# buffer.net
KiCad netlist of a schematic drawn in Altium Designer
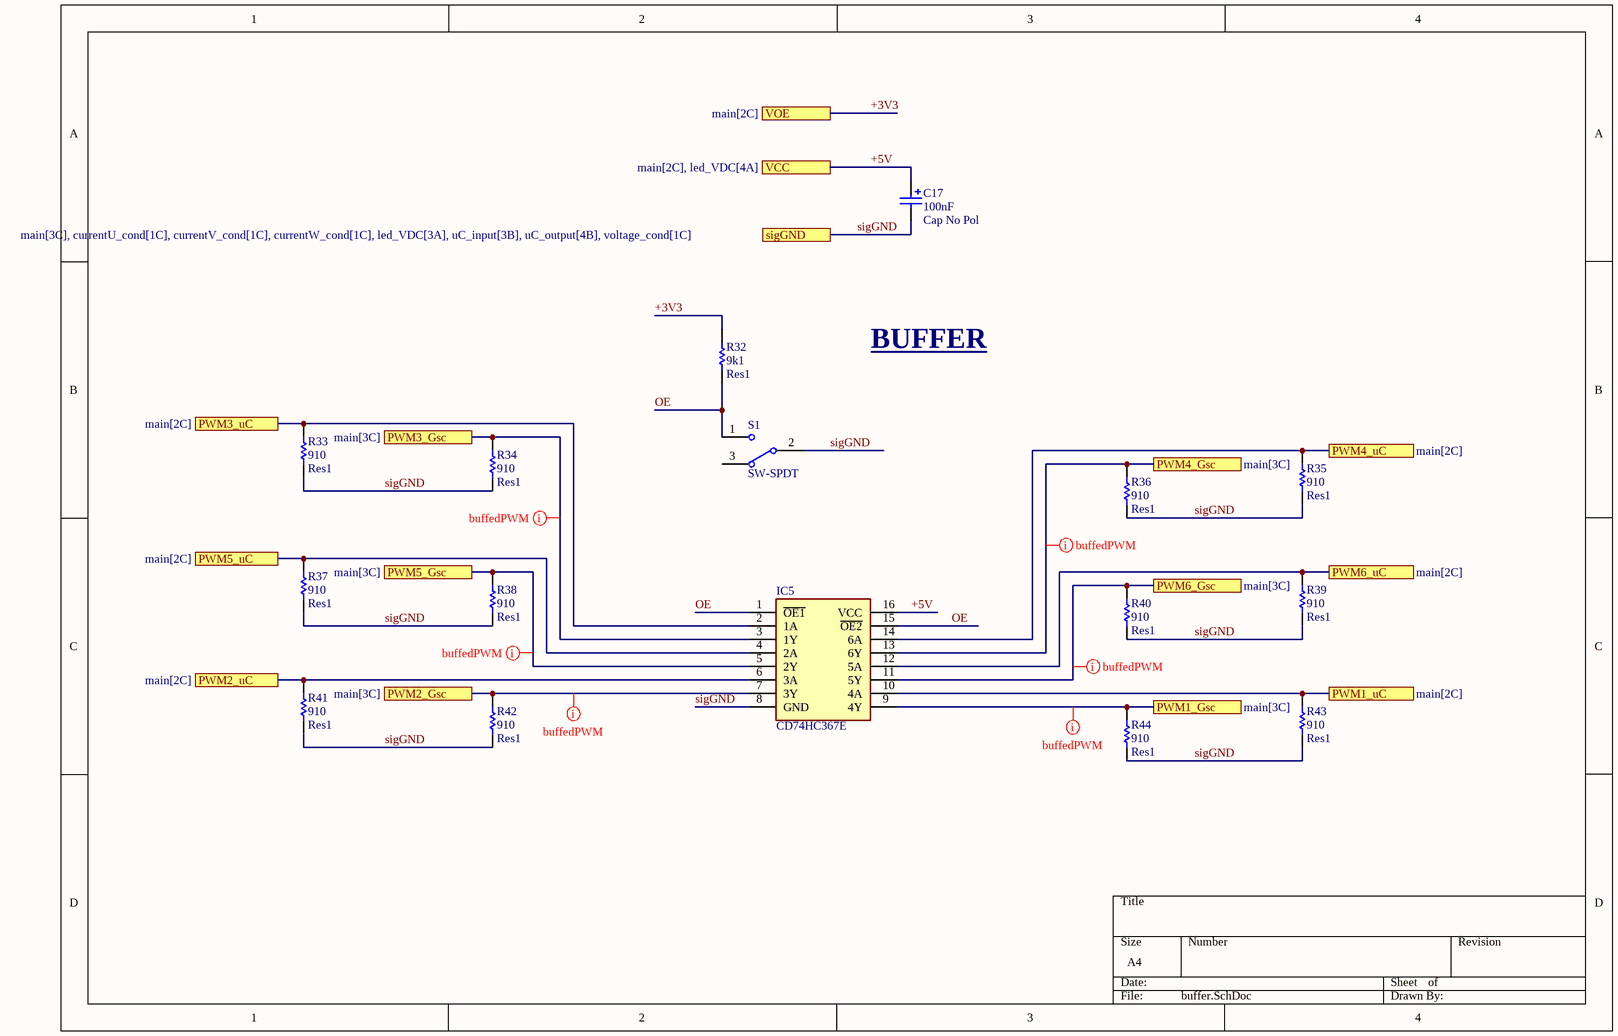
[diagram p0: buffer.SchDoc]

(export (version "E")
  (design (tool "Eeschema 10.0.6"))
  (components
    (comp (ref "C17")
      (value "Cap No Pol")
      (footprint "RAD-0.1_mod")
      (description "Polarized Capacitor (Radial)")
      (fields (field (name "ALTIUM_VALUE") "100nF") (field (name "PUBLISHER") "Altium Limited"))
      (libsource (lib "LABSTEPS_Project") (part "Cap No Pol"))
    )
    (comp (ref "IC5")
      (value "CD74HC367E")
      (footprint "DIP-16_mod")
      (description "Integrated Circuit")
      (fields (field (name "MOUSER PART NUMBER") "595-CD74HC367E"))
      (libsource (lib "SamacSys") (part "CD74HC367E"))
    )
    (comp (ref "R32")
      (value "Res1")
      (footprint "AXIAL-0.3_mod")
      (description "Resistor")
      (fields (field (name "ALTIUM_VALUE") "9k1") (field (name "PUBLISHER") "Altium Limited"))
      (libsource (lib "LABSTEPS_Project") (part "Res1"))
    )
    (comp (ref "R33")
      (value "Res1")
      (footprint "AXIAL-0.3_mod")
      (description "Resistor")
      (fields (field (name "ALTIUM_VALUE") "910") (field (name "PUBLISHER") "Altium Limited"))
      (libsource (lib "LABSTEPS_Project") (part "Res1"))
    )
    (comp (ref "R34")
      (value "Res1")
      (footprint "AXIAL-0.3_mod")
      (description "Resistor")
      (fields (field (name "ALTIUM_VALUE") "910") (field (name "PUBLISHER") "Altium Limited"))
      (libsource (lib "LABSTEPS_Project") (part "Res1"))
    )
    (comp (ref "R35")
      (value "Res1")
      (footprint "AXIAL-0.3_mod")
      (description "Resistor")
      (fields (field (name "ALTIUM_VALUE") "910") (field (name "PUBLISHER") "Altium Limited"))
      (libsource (lib "LABSTEPS_Project") (part "Res1"))
    )
    (comp (ref "R36")
      (value "Res1")
      (footprint "AXIAL-0.3_mod")
      (description "Resistor")
      (fields (field (name "ALTIUM_VALUE") "910") (field (name "PUBLISHER") "Altium Limited"))
      (libsource (lib "LABSTEPS_Project") (part "Res1"))
    )
    (comp (ref "R37")
      (value "Res1")
      (footprint "AXIAL-0.3_mod")
      (description "Resistor")
      (fields (field (name "ALTIUM_VALUE") "910") (field (name "PUBLISHER") "Altium Limited"))
      (libsource (lib "LABSTEPS_Project") (part "Res1"))
    )
    (comp (ref "R38")
      (value "Res1")
      (footprint "AXIAL-0.3_mod")
      (description "Resistor")
      (fields (field (name "ALTIUM_VALUE") "910") (field (name "PUBLISHER") "Altium Limited"))
      (libsource (lib "LABSTEPS_Project") (part "Res1"))
    )
    (comp (ref "R39")
      (value "Res1")
      (footprint "AXIAL-0.3_mod")
      (description "Resistor")
      (fields (field (name "ALTIUM_VALUE") "910") (field (name "PUBLISHER") "Altium Limited"))
      (libsource (lib "LABSTEPS_Project") (part "Res1"))
    )
    (comp (ref "R40")
      (value "Res1")
      (footprint "AXIAL-0.3_mod")
      (description "Resistor")
      (fields (field (name "ALTIUM_VALUE") "910") (field (name "PUBLISHER") "Altium Limited"))
      (libsource (lib "LABSTEPS_Project") (part "Res1"))
    )
    (comp (ref "R41")
      (value "Res1")
      (footprint "AXIAL-0.3_mod")
      (description "Resistor")
      (fields (field (name "ALTIUM_VALUE") "910") (field (name "PUBLISHER") "Altium Limited"))
      (libsource (lib "LABSTEPS_Project") (part "Res1"))
    )
    (comp (ref "R42")
      (value "Res1")
      (footprint "AXIAL-0.3_mod")
      (description "Resistor")
      (fields (field (name "ALTIUM_VALUE") "910") (field (name "PUBLISHER") "Altium Limited"))
      (libsource (lib "LABSTEPS_Project") (part "Res1"))
    )
    (comp (ref "R43")
      (value "Res1")
      (footprint "AXIAL-0.3_mod")
      (description "Resistor")
      (fields (field (name "ALTIUM_VALUE") "910") (field (name "PUBLISHER") "Altium Limited"))
      (libsource (lib "LABSTEPS_Project") (part "Res1"))
    )
    (comp (ref "R44")
      (value "Res1")
      (footprint "AXIAL-0.3_mod")
      (description "Resistor")
      (fields (field (name "ALTIUM_VALUE") "910") (field (name "PUBLISHER") "Altium Limited"))
      (libsource (lib "LABSTEPS_Project") (part "Res1"))
    )
    (comp (ref "S1")
      (value "SW-SPDT")
      (footprint "MHDR1X3_mod")
      (description "SPDT Subminiature Toggle Switch, Right Angle Mounting, Vertical Actuation")
      (fields (field (name "PUBLISHER") "Altium Limited"))
      (libsource (lib "LABSTEPS_Project") (part "SW-SPDT"))
    )
  )
  (nets
    (net (code "1") (name "/+3V3") (class "Default")
      (node (ref "R32") (pin "2") (pinfunction "2_2") (pintype "passive"))
    )
    (net (code "2") (name "/+5V") (class "Default")
      (node (ref "C17") (pin "1") (pinfunction "1_1") (pintype "passive"))
      (node (ref "IC5") (pin "16") (pinfunction "VCC_16") (pintype "passive"))
    )
    (net (code "3") (name "/OE") (class "Default")
      (node (ref "IC5") (pin "1") (pinfunction "~{OE1}_1") (pintype "passive"))
      (node (ref "IC5") (pin "15") (pinfunction "~{OE2}_15") (pintype "passive"))
      (node (ref "R32") (pin "1") (pinfunction "1_1") (pintype "passive"))
      (node (ref "S1") (pin "1") (pinfunction "1_1") (pintype "passive"))
    )
    (net (code "4") (name "/PWM1_Gsc") (class "Default")
      (node (ref "IC5") (pin "9") (pinfunction "4Y_9") (pintype "passive"))
      (node (ref "R44") (pin "2") (pinfunction "2_2") (pintype "passive"))
    )
    (net (code "5") (name "/PWM1_uC") (class "Default")
      (node (ref "IC5") (pin "10") (pinfunction "4A_10") (pintype "passive"))
      (node (ref "R43") (pin "2") (pinfunction "2_2") (pintype "passive"))
    )
    (net (code "6") (name "/PWM2_Gsc") (class "Default")
      (node (ref "IC5") (pin "7") (pinfunction "3Y_7") (pintype "passive"))
      (node (ref "R42") (pin "2") (pinfunction "2_2") (pintype "passive"))
    )
    (net (code "7") (name "/PWM2_uC") (class "Default")
      (node (ref "IC5") (pin "6") (pinfunction "3A_6") (pintype "passive"))
      (node (ref "R41") (pin "2") (pinfunction "2_2") (pintype "passive"))
    )
    (net (code "8") (name "/PWM3_Gsc") (class "Default")
      (node (ref "IC5") (pin "3") (pinfunction "1Y_3") (pintype "passive"))
      (node (ref "R34") (pin "2") (pinfunction "2_2") (pintype "passive"))
    )
    (net (code "9") (name "/PWM3_uC") (class "Default")
      (node (ref "IC5") (pin "2") (pinfunction "1A_2") (pintype "passive"))
      (node (ref "R33") (pin "2") (pinfunction "2_2") (pintype "passive"))
    )
    (net (code "10") (name "/PWM4_Gsc") (class "Default")
      (node (ref "IC5") (pin "13") (pinfunction "6Y_13") (pintype "passive"))
      (node (ref "R36") (pin "2") (pinfunction "2_2") (pintype "passive"))
    )
    (net (code "11") (name "/PWM4_uC") (class "Default")
      (node (ref "IC5") (pin "14") (pinfunction "6A_14") (pintype "passive"))
      (node (ref "R35") (pin "2") (pinfunction "2_2") (pintype "passive"))
    )
    (net (code "12") (name "/PWM5_Gsc") (class "Default")
      (node (ref "IC5") (pin "5") (pinfunction "2Y_5") (pintype "passive"))
      (node (ref "R38") (pin "2") (pinfunction "2_2") (pintype "passive"))
    )
    (net (code "13") (name "/PWM5_uC") (class "Default")
      (node (ref "IC5") (pin "4") (pinfunction "2A_4") (pintype "passive"))
      (node (ref "R37") (pin "2") (pinfunction "2_2") (pintype "passive"))
    )
    (net (code "14") (name "/PWM6_Gsc") (class "Default")
      (node (ref "IC5") (pin "11") (pinfunction "5Y_11") (pintype "passive"))
      (node (ref "R40") (pin "2") (pinfunction "2_2") (pintype "passive"))
    )
    (net (code "15") (name "/PWM6_uC") (class "Default")
      (node (ref "IC5") (pin "12") (pinfunction "5A_12") (pintype "passive"))
      (node (ref "R39") (pin "2") (pinfunction "2_2") (pintype "passive"))
    )
    (net (code "16") (name "/sigGND") (class "Default")
      (node (ref "C17") (pin "2") (pinfunction "2_2") (pintype "passive"))
      (node (ref "IC5") (pin "8") (pinfunction "GND_8") (pintype "passive"))
      (node (ref "R33") (pin "1") (pinfunction "1_1") (pintype "passive"))
      (node (ref "R34") (pin "1") (pinfunction "1_1") (pintype "passive"))
      (node (ref "R35") (pin "1") (pinfunction "1_1") (pintype "passive"))
      (node (ref "R36") (pin "1") (pinfunction "1_1") (pintype "passive"))
      (node (ref "R37") (pin "1") (pinfunction "1_1") (pintype "passive"))
      (node (ref "R38") (pin "1") (pinfunction "1_1") (pintype "passive"))
      (node (ref "R39") (pin "1") (pinfunction "1_1") (pintype "passive"))
      (node (ref "R40") (pin "1") (pinfunction "1_1") (pintype "passive"))
      (node (ref "R41") (pin "1") (pinfunction "1_1") (pintype "passive"))
      (node (ref "R42") (pin "1") (pinfunction "1_1") (pintype "passive"))
      (node (ref "R43") (pin "1") (pinfunction "1_1") (pintype "passive"))
      (node (ref "R44") (pin "1") (pinfunction "1_1") (pintype "passive"))
      (node (ref "S1") (pin "2") (pinfunction "2_2") (pintype "passive"))
    )
    (net (code "17") (name "unconnected-(S1-Pad3)") (class "Default")
      (node (ref "S1") (pin "3") (pinfunction "3_3") (pintype "passive"))
    )
  )
)
